# board.net
KiCad netlist of a schematic drawn in EAGLE
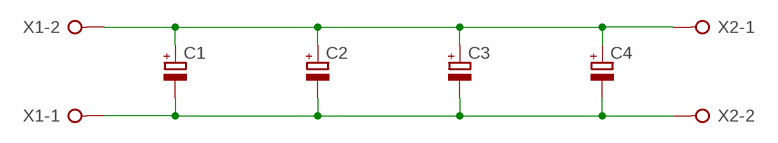
[diagram p0: schematic, sheet 1]

(export (version "E")
  (design (tool "Eeschema 10.0.6"))
  (components
    (comp (ref "C1")
      (value "CPOL-EUE10-30")
      (footprint "eagle-import:EB30D")
      (libsource (lib "eagle-import") (part "CPOL-EUE10-30"))
    )
    (comp (ref "C2")
      (value "CPOL-EUE10-22.5")
      (footprint "eagle-import:EB22,5D")
      (libsource (lib "eagle-import") (part "CPOL-EUE10-22.5"))
    )
    (comp (ref "C3")
      (value "CPOL-EUE10-22.5")
      (footprint "eagle-import:EB22,5D")
      (libsource (lib "eagle-import") (part "CPOL-EUE10-22.5"))
    )
    (comp (ref "C4")
      (value "CPOL-EUE10-22.5")
      (footprint "eagle-import:EB22,5D")
      (libsource (lib "eagle-import") (part "CPOL-EUE10-22.5"))
    )
    (comp (ref "X1")
      (value "W237-02P")
      (footprint "eagle-import:W237-132")
      (libsource (lib "eagle-import") (part "W237-02P"))
    )
    (comp (ref "X2")
      (value "W237-02P")
      (footprint "eagle-import:W237-132")
      (libsource (lib "eagle-import") (part "W237-02P"))
    )
  )
  (nets
    (net (code "1") (name "Net-(X1A-KL)") (class "Default")
      (node (ref "C1") (pin "-") (pinfunction "-_-") (pintype "passive"))
      (node (ref "C2") (pin "-") (pinfunction "-_-") (pintype "passive"))
      (node (ref "C3") (pin "-") (pinfunction "-_-") (pintype "passive"))
      (node (ref "C4") (pin "-") (pinfunction "-_-") (pintype "passive"))
      (node (ref "X1") (pin "1") (pinfunction "KL_1") (pintype "passive"))
      (node (ref "X2") (pin "2") (pinfunction "KL_2") (pintype "passive"))
    )
    (net (code "2") (name "Net-(X1B-KL)") (class "Default")
      (node (ref "C1") (pin "+") (pinfunction "+_+") (pintype "passive"))
      (node (ref "C2") (pin "+") (pinfunction "+_+") (pintype "passive"))
      (node (ref "C3") (pin "+") (pinfunction "+_+") (pintype "passive"))
      (node (ref "C4") (pin "+") (pinfunction "+_+") (pintype "passive"))
      (node (ref "X1") (pin "2") (pinfunction "KL_2") (pintype "passive"))
      (node (ref "X2") (pin "1") (pinfunction "KL_1") (pintype "passive"))
    )
  )
)
